# Gagabiro_main.net
KiCad netlist of a schematic drawn in Altium Designer
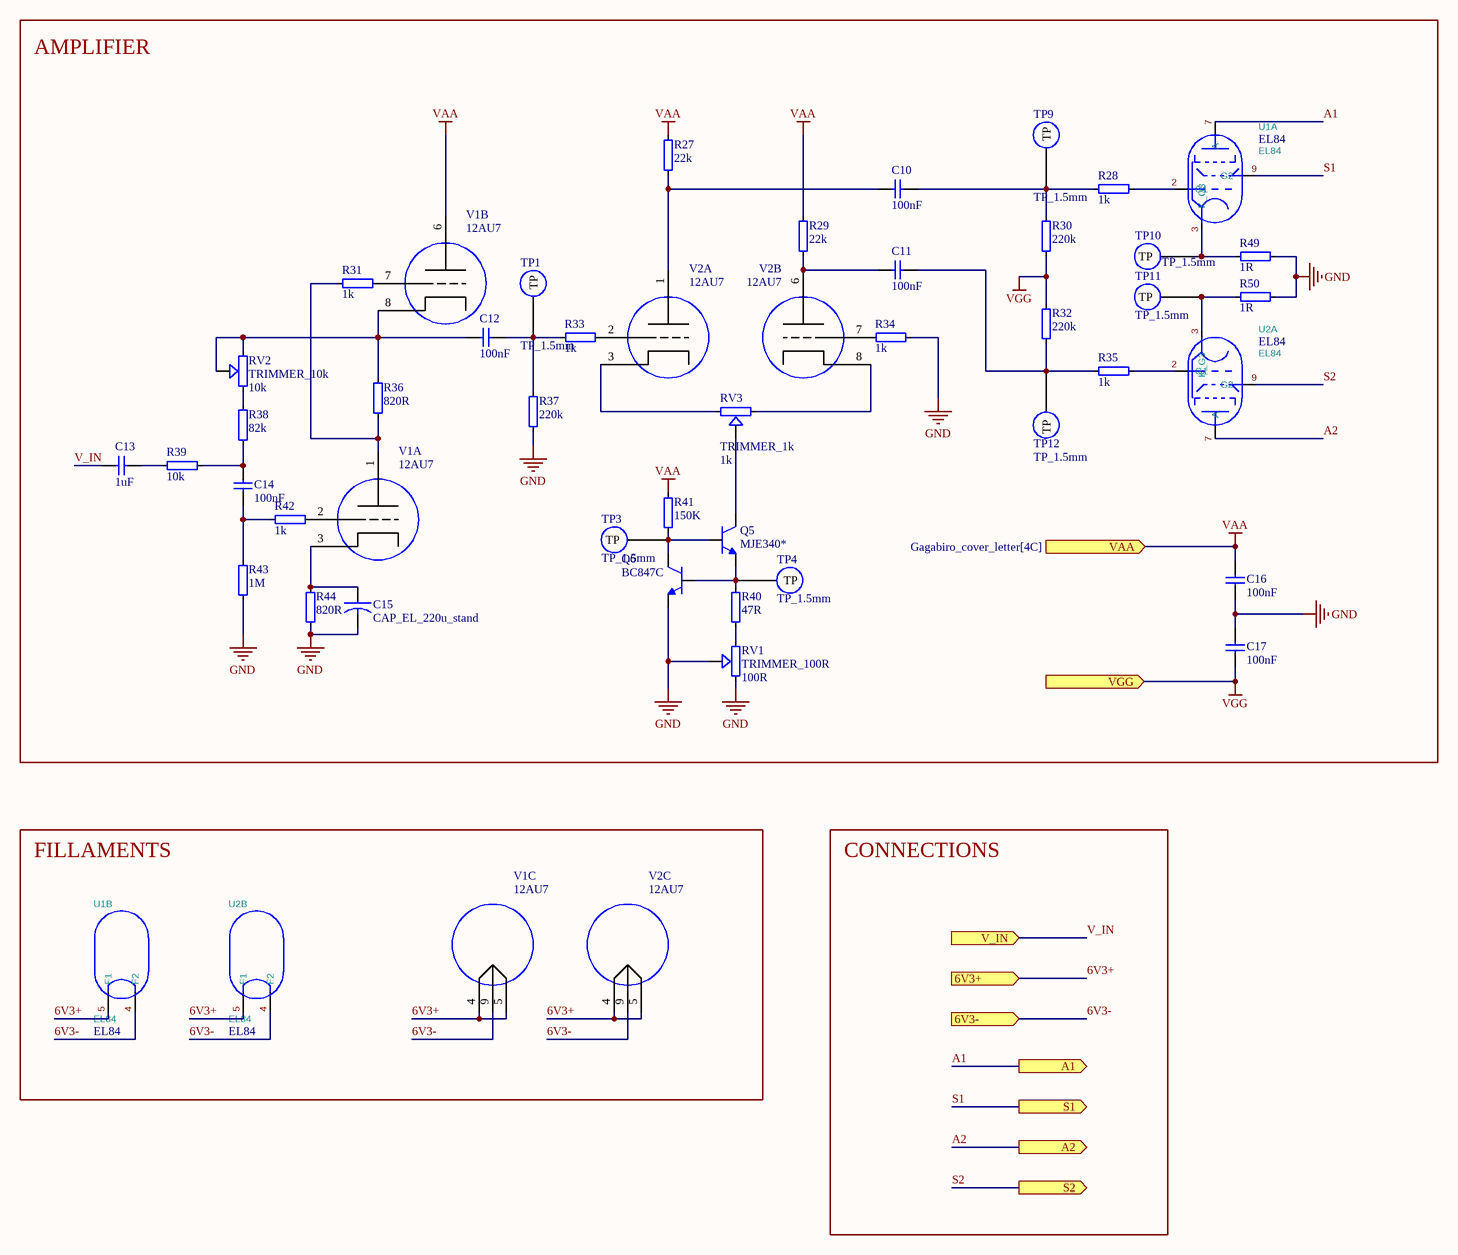
[diagram p0: Gagabiro_main.SchDoc]

(export (version "E")
  (design (tool "Eeschema 10.0.6"))
  (components
    (comp (ref "C10")
      (value "100nF")
      (footprint "CAP_panassonic_100n_450V")
      (description "Capacitor, Silver Mica")
      (fields (field (name "PART NUMBER") "CMICA_47PF"))
      (libsource (lib "Persephone_Integrated_Library") (part "CAP_POLY_100n"))
    )
    (comp (ref "C11")
      (value "100nF")
      (footprint "CAP_panassonic_100n_450V")
      (description "Capacitor, Silver Mica")
      (fields (field (name "PART NUMBER") "CMICA_47PF"))
      (libsource (lib "Persephone_Integrated_Library") (part "CAP_POLY_100n"))
    )
    (comp (ref "C12")
      (value "100nF")
      (footprint "CAP_panassonic_100n_450V")
      (description "Capacitor, Silver Mica")
      (fields (field (name "PART NUMBER") "CMICA_47PF"))
      (libsource (lib "Persephone_Integrated_Library") (part "CAP_POLY_100n"))
    )
    (comp (ref "C13")
      (value "1uF")
      (footprint "CAP_panassonic_1u_450V")
      (description "Capacitor, Silver Mica")
      (fields (field (name "PART NUMBER") "CMICA_47PF"))
      (libsource (lib "Persephone_Integrated_Library") (part "CAP_POLY_1u"))
    )
    (comp (ref "C14")
      (value "100nF")
      (footprint "CAP_panassonic_100n_450V")
      (description "Capacitor, Silver Mica")
      (fields (field (name "PART NUMBER") "CMICA_47PF"))
      (libsource (lib "Persephone_Integrated_Library") (part "CAP_POLY_100n"))
    )
    (comp (ref "C15")
      (value "CAP_EL_220u_stand")
      (footprint "CAPPRD500W50D630H1120_stand")
      (description "220F 16V Aluminum Electrolytic Capacitors Radial, Can 1000 Hrs @ 105C")
      (fields (field (name "MP") "EEU-HD1C221B") (field (name "MF") "Panasonic"))
      (libsource (lib "Persephone_Integrated_Library") (part "CAP_EL_220u_stand"))
    )
    (comp (ref "C16")
      (value "100nF")
      (footprint "CAP_panassonic_100n_450V")
      (description "Capacitor, Silver Mica")
      (fields (field (name "PART NUMBER") "CMICA_47PF"))
      (libsource (lib "Persephone_Integrated_Library") (part "CAP_POLY_100n"))
    )
    (comp (ref "C17")
      (value "100nF")
      (footprint "CAP_panassonic_100n_450V")
      (description "Capacitor, Silver Mica")
      (fields (field (name "PART NUMBER") "CMICA_47PF"))
      (libsource (lib "Persephone_Integrated_Library") (part "CAP_POLY_100n"))
    )
    (comp (ref "Q5")
      (value "MJE340*")
      (footprint "TO126")
      (description "Bipolar (BJT) Transistor NPN 300 V 500 mA - 20.8 W Through Hole SOT-32-3")
      (fields (field (name "MF") "STMicroelectronics") (field (name "MP") "MJE340"))
      (libsource (lib "Persephone_Integrated_Library") (part "MJE340*"))
    )
    (comp (ref "Q6")
      (value "BC847C")
      (footprint "TRANS_BC847C")
      (description "Bipolar (BJT) Transistor NPN 45 V 100 mA 300MHz 250 mW Surface Mount SOT-23-3 (TO-236)")
      (fields (field (name "MF") "Diotec Semiconductor"))
      (libsource (lib "Persephone") (part "BC847C"))
    )
    (comp (ref "R27")
      (value "22k")
      (footprint "RES_2W_vertical")
      (description "Resistor, 2W")
      (fields (field (name "PART NUMBER") "R2W") (field (name "AUTHOR") "colombari"))
      (libsource (lib "Gagabiro_Integrated_Library") (part "R_2W_vertical_22k"))
    )
    (comp (ref "R28")
      (value "1k")
      (footprint "RES_2W_vertical")
      (description "Resistor, 2W")
      (fields (field (name "PART NUMBER") "R2W") (field (name "AUTHOR") "colombari"))
      (libsource (lib "Gagabiro_Integrated_Library") (part "R_2W_vertical_1k"))
    )
    (comp (ref "R29")
      (value "22k")
      (footprint "RES_2W_vertical")
      (description "Resistor, 2W")
      (fields (field (name "PART NUMBER") "R2W") (field (name "AUTHOR") "colombari"))
      (libsource (lib "Gagabiro_Integrated_Library") (part "R_2W_vertical_22k"))
    )
    (comp (ref "R30")
      (value "220k")
      (footprint "RES_2W_vertical")
      (description "Resistor, 2W")
      (fields (field (name "PART NUMBER") "R2W") (field (name "AUTHOR") "colombari"))
      (libsource (lib "Gagabiro_Integrated_Library") (part "R_2W_vertical_220k"))
    )
    (comp (ref "R31")
      (value "1k")
      (footprint "RES_2W_vertical")
      (description "Resistor, 2W")
      (fields (field (name "PART NUMBER") "R2W") (field (name "AUTHOR") "colombari"))
      (libsource (lib "Gagabiro_Integrated_Library") (part "R_2W_vertical_1k"))
    )
    (comp (ref "R32")
      (value "220k")
      (footprint "RES_2W_vertical")
      (description "Resistor, 2W")
      (fields (field (name "PART NUMBER") "R2W") (field (name "AUTHOR") "colombari"))
      (libsource (lib "Gagabiro_Integrated_Library") (part "R_2W_vertical_220k"))
    )
    (comp (ref "R33")
      (value "1k")
      (footprint "RES_2W_vertical")
      (description "Resistor, 2W")
      (fields (field (name "PART NUMBER") "R2W") (field (name "AUTHOR") "colombari"))
      (libsource (lib "Gagabiro_Integrated_Library") (part "R_2W_vertical_1k"))
    )
    (comp (ref "R34")
      (value "1k")
      (footprint "RES_2W_vertical")
      (description "Resistor, 2W")
      (fields (field (name "PART NUMBER") "R2W") (field (name "AUTHOR") "colombari"))
      (libsource (lib "Gagabiro_Integrated_Library") (part "R_2W_vertical_1k"))
    )
    (comp (ref "R35")
      (value "1k")
      (footprint "RES_2W_vertical")
      (description "Resistor, 2W")
      (fields (field (name "PART NUMBER") "R2W") (field (name "AUTHOR") "colombari"))
      (libsource (lib "Gagabiro_Integrated_Library") (part "R_2W_vertical_1k"))
    )
    (comp (ref "R36")
      (value "820R")
      (footprint "RES_2W_vertical")
      (description "Resistor, 2W")
      (fields (field (name "PART NUMBER") "R2W") (field (name "AUTHOR") "colombari"))
      (libsource (lib "Gagabiro_Integrated_Library") (part "R_2W_vertical_820R"))
    )
    (comp (ref "R37")
      (value "220k")
      (footprint "RES_2W_vertical")
      (description "Resistor, 2W")
      (fields (field (name "PART NUMBER") "R2W") (field (name "AUTHOR") "colombari"))
      (libsource (lib "Gagabiro_Integrated_Library") (part "R_2W_vertical_220k"))
    )
    (comp (ref "R38")
      (value "82k")
      (footprint "RES_2W_vertical")
      (description "Resistor, 2W")
      (fields (field (name "PART NUMBER") "R2W") (field (name "AUTHOR") "colombari"))
      (libsource (lib "Gagabiro_Integrated_Library") (part "R_2W_vertical_82k"))
    )
    (comp (ref "R39")
      (value "10k")
      (footprint "RES_2W_vertical")
      (description "Resistor, 2W")
      (fields (field (name "PART NUMBER") "R2W") (field (name "AUTHOR") "colombari"))
      (libsource (lib "Gagabiro_Integrated_Library") (part "R_2W_vertical_10k"))
    )
    (comp (ref "R40")
      (value "47R")
      (footprint "RES_2W_vertical")
      (description "Resistor, 2W")
      (fields (field (name "PART NUMBER") "R2W") (field (name "AUTHOR") "colombari"))
      (libsource (lib "Gagabiro_Integrated_Library") (part "R_2W_vertical_47R"))
    )
    (comp (ref "R41")
      (value "150K")
      (footprint "RES_2W_vertical")
      (description "Resistor, 2W")
      (fields (field (name "PART NUMBER") "R2W") (field (name "AUTHOR") "colombari"))
      (libsource (lib "Gagabiro_Integrated_Library") (part "R_2W_vertical_150K"))
    )
    (comp (ref "R42")
      (value "1k")
      (footprint "RES_2W_vertical")
      (description "Resistor, 2W")
      (fields (field (name "PART NUMBER") "R2W") (field (name "AUTHOR") "colombari"))
      (libsource (lib "Gagabiro_Integrated_Library") (part "R_2W_vertical_1k"))
    )
    (comp (ref "R43")
      (value "1M")
      (footprint "RES_2W_vertical")
      (description "Resistor, 2W")
      (fields (field (name "PART NUMBER") "R2W") (field (name "AUTHOR") "colombari"))
      (libsource (lib "Gagabiro_Integrated_Library") (part "R_2W_vertical_1M"))
    )
    (comp (ref "R44")
      (value "820R")
      (footprint "RES_2W_vertical")
      (description "Resistor, 2W")
      (fields (field (name "PART NUMBER") "R2W") (field (name "AUTHOR") "colombari"))
      (libsource (lib "Gagabiro_Integrated_Library") (part "R_2W_vertical_820R"))
    )
    (comp (ref "R49")
      (value "1R")
      (footprint "RES_2W_vertical")
      (description "Resistor, 2W")
      (fields (field (name "PART NUMBER") "R2W") (field (name "AUTHOR") "colombari"))
      (libsource (lib "Gagabiro_Integrated_Library") (part "R_2W_vertical_1R"))
    )
    (comp (ref "R50")
      (value "1R")
      (footprint "RES_2W_vertical")
      (description "Resistor, 2W")
      (fields (field (name "PART NUMBER") "R2W") (field (name "AUTHOR") "colombari"))
      (libsource (lib "Gagabiro_Integrated_Library") (part "R_2W_vertical_1R"))
    )
    (comp (ref "RV1")
      (value "TRIMMER_100R")
      (footprint "TRIM_PV36W204C01B00 - duplicate")
      (description "TRIMMER")
      (fields
        (field (name "MF") "Bourns Electronics")
        (field (name "MP") "PV36W204C01B00.")
        (field (name "ALTIUM_VALUE") "100R")
      )
      (libsource (lib "Persephone") (part "TRIMMER_100R"))
    )
    (comp (ref "RV2")
      (value "TRIMMER_10k")
      (footprint "TRIM_PV36W204C01B00 - duplicate")
      (description "TRIMMER")
      (fields
        (field (name "MF") "Bourns Electronics")
        (field (name "MP") "PV36W204C01B00.")
        (field (name "ALTIUM_VALUE") "10k")
      )
      (libsource (lib "Persephone_Integrated_Library") (part "TRIMMER_10k"))
    )
    (comp (ref "RV3")
      (value "TRIMMER_1k")
      (footprint "TRIM_PV36W204C01B00 - duplicate")
      (description "TRIMMER")
      (fields
        (field (name "MF") "Bourns Electronics")
        (field (name "MP") "PV36W204C01B00.")
        (field (name "ALTIUM_VALUE") "1k")
      )
      (libsource (lib "Persephone_Integrated_Library") (part "TRIMMER_1k"))
    )
    (comp (ref "TP1")
      (value "TP_1.5mm")
      (footprint "test_point_1.5mm")
      (libsource (lib "Gagabiro_Integrated_Library") (part "TP_1.5mm"))
    )
    (comp (ref "TP3")
      (value "TP_1.5mm")
      (footprint "test_point_1.5mm")
      (libsource (lib "Gagabiro_Integrated_Library") (part "TP_1.5mm"))
    )
    (comp (ref "TP4")
      (value "TP_1.5mm")
      (footprint "test_point_1.5mm")
      (libsource (lib "Gagabiro_Integrated_Library") (part "TP_1.5mm"))
    )
    (comp (ref "TP9")
      (value "TP_1.5mm")
      (footprint "test_point_1.5mm")
      (libsource (lib "Gagabiro_Integrated_Library") (part "TP_1.5mm"))
    )
    (comp (ref "TP10")
      (value "TP_1.5mm")
      (footprint "test_point_1.5mm")
      (libsource (lib "Gagabiro_Integrated_Library") (part "TP_1.5mm"))
    )
    (comp (ref "TP11")
      (value "TP_1.5mm")
      (footprint "test_point_1.5mm")
      (libsource (lib "Gagabiro_Integrated_Library") (part "TP_1.5mm"))
    )
    (comp (ref "TP12")
      (value "TP_1.5mm")
      (footprint "test_point_1.5mm")
      (libsource (lib "Gagabiro_Integrated_Library") (part "TP_1.5mm"))
    )
    (comp (ref "U1")
      (value "EL84")
      (footprint "EL84")
      (fields (field (name "ALTIUM_VALUE") "EL84"))
      (libsource (lib "") (part "EL84_1"))
    )
    (comp (ref "U2")
      (value "EL84")
      (footprint "EL84")
      (fields (field (name "ALTIUM_VALUE") "EL84"))
      (libsource (lib "Gagabiro_Integrated_Library") (part "EL84"))
    )
    (comp (ref "V1")
      (value "12AU7")
      (footprint "12A_7")
      (description "TUNGSOL 12AU7 NEW PRD PREAMP TB")
      (fields (field (name "MF") "RCA") (field (name "MP") "12AX7"))
      (libsource (lib "Gagabiro_Integrated_Library") (part "12AU7"))
    )
    (comp (ref "V2")
      (value "12AU7")
      (footprint "12A_7")
      (description "TUNGSOL 12AU7 NEW PRD PREAMP TB")
      (fields (field (name "MF") "RCA") (field (name "MP") "12AX7"))
      (libsource (lib "") (part "12AU7_1"))
    )
  )
  (nets
    (net (code "1") (name "/6V3+") (class "Default")
      (node (ref "U1") (pin "5") (pinfunction "F1_5") (pintype "passive"))
      (node (ref "U2") (pin "5") (pinfunction "F1_5") (pintype "passive"))
      (node (ref "V1") (pin "4") (pinfunction "4_4") (pintype "passive"))
      (node (ref "V1") (pin "5") (pinfunction "5_5") (pintype "passive"))
      (node (ref "V2") (pin "4") (pinfunction "4_4") (pintype "passive"))
      (node (ref "V2") (pin "5") (pinfunction "5_5") (pintype "passive"))
    )
    (net (code "2") (name "/6V3-") (class "Default")
      (node (ref "U1") (pin "4") (pinfunction "F2_4") (pintype "passive"))
      (node (ref "U2") (pin "4") (pinfunction "F2_4") (pintype "passive"))
      (node (ref "V1") (pin "9") (pinfunction "9_9") (pintype "passive"))
      (node (ref "V2") (pin "9") (pinfunction "9_9") (pintype "passive"))
    )
    (net (code "3") (name "/A1") (class "Default")
      (node (ref "U1") (pin "7") (pinfunction "A_7") (pintype "passive"))
    )
    (net (code "4") (name "/A2") (class "Default")
      (node (ref "U2") (pin "7") (pinfunction "A_7") (pintype "passive"))
    )
    (net (code "5") (name "/S1") (class "Default")
      (node (ref "U1") (pin "9") (pinfunction "G2_9") (pintype "passive"))
    )
    (net (code "6") (name "/S2") (class "Default")
      (node (ref "U2") (pin "9") (pinfunction "G2_9") (pintype "passive"))
    )
    (net (code "7") (name "/V_IN") (class "Default")
      (node (ref "C13") (pin "1") (pinfunction "1_1") (pintype "passive"))
    )
    (net (code "8") (name "GND") (class "Default")
      (node (ref "C15") (pin "N") (pinfunction "N_N") (pintype "passive"))
      (node (ref "C16") (pin "1") (pinfunction "1_1") (pintype "passive"))
      (node (ref "C17") (pin "1") (pinfunction "1_1") (pintype "passive"))
      (node (ref "Q6") (pin "2") (pinfunction "E_2") (pintype "passive"))
      (node (ref "R34") (pin "2") (pinfunction "2_2") (pintype "passive"))
      (node (ref "R37") (pin "1") (pinfunction "1_1") (pintype "passive"))
      (node (ref "R43") (pin "1") (pinfunction "1_1") (pintype "passive"))
      (node (ref "R44") (pin "1") (pinfunction "1_1") (pintype "passive"))
      (node (ref "R49") (pin "2") (pinfunction "2_2") (pintype "passive"))
      (node (ref "R50") (pin "2") (pinfunction "2_2") (pintype "passive"))
      (node (ref "RV1") (pin "1") (pinfunction "1_1") (pintype "passive"))
      (node (ref "RV1") (pin "2") (pinfunction "2_2") (pintype "passive"))
    )
    (net (code "9") (name "Net-(C10-Pad1)") (class "Default")
      (node (ref "C10") (pin "1") (pinfunction "1_1") (pintype "passive"))
      (node (ref "R27") (pin "1") (pinfunction "1_1") (pintype "passive"))
      (node (ref "V2") (pin "1") (pinfunction "1_1") (pintype "passive"))
    )
    (net (code "10") (name "Net-(C11-Pad1)") (class "Default")
      (node (ref "C11") (pin "1") (pinfunction "1_1") (pintype "passive"))
      (node (ref "R29") (pin "1") (pinfunction "1_1") (pintype "passive"))
      (node (ref "V2") (pin "6") (pinfunction "6_6") (pintype "passive"))
    )
    (net (code "11") (name "Net-(C12-Pad1)") (class "Default")
      (node (ref "C12") (pin "1") (pinfunction "1_1") (pintype "passive"))
      (node (ref "R36") (pin "2") (pinfunction "2_2") (pintype "passive"))
      (node (ref "RV2") (pin "2") (pinfunction "2_2") (pintype "passive"))
      (node (ref "RV2") (pin "3") (pinfunction "3_3") (pintype "passive"))
      (node (ref "V1") (pin "8") (pinfunction "8_8") (pintype "passive"))
    )
    (net (code "12") (name "Net-(C13-Pad2)") (class "Default")
      (node (ref "C13") (pin "2") (pinfunction "2_2") (pintype "passive"))
      (node (ref "R39") (pin "1") (pinfunction "1_1") (pintype "passive"))
    )
    (net (code "13") (name "Net-(C14-Pad1)") (class "Default")
      (node (ref "C14") (pin "1") (pinfunction "1_1") (pintype "passive"))
      (node (ref "R42") (pin "1") (pinfunction "1_1") (pintype "passive"))
      (node (ref "R43") (pin "2") (pinfunction "2_2") (pintype "passive"))
    )
    (net (code "14") (name "Net-(C14-Pad2)") (class "Default")
      (node (ref "C14") (pin "2") (pinfunction "2_2") (pintype "passive"))
      (node (ref "R38") (pin "1") (pinfunction "1_1") (pintype "passive"))
      (node (ref "R39") (pin "2") (pinfunction "2_2") (pintype "passive"))
    )
    (net (code "15") (name "Net-(C15-PadP)") (class "Default")
      (node (ref "C15") (pin "P") (pinfunction "P_P") (pintype "passive"))
      (node (ref "R44") (pin "2") (pinfunction "2_2") (pintype "passive"))
      (node (ref "V1") (pin "3") (pinfunction "3_3") (pintype "passive"))
    )
    (net (code "16") (name "Net-(Q5-B)") (class "Default")
      (node (ref "Q5") (pin "3") (pinfunction "B_3") (pintype "passive"))
      (node (ref "Q6") (pin "3") (pinfunction "C_3") (pintype "passive"))
      (node (ref "R41") (pin "1") (pinfunction "1_1") (pintype "passive"))
      (node (ref "TP3") (pin "1") (pinfunction "TP_1") (pintype "passive"))
    )
    (net (code "17") (name "Net-(Q5-C)") (class "Default")
      (node (ref "Q5") (pin "2") (pinfunction "C_2") (pintype "passive"))
      (node (ref "RV3") (pin "2") (pinfunction "2_2") (pintype "passive"))
    )
    (net (code "18") (name "Net-(Q5-E)") (class "Default")
      (node (ref "Q5") (pin "1") (pinfunction "E_1") (pintype "passive"))
      (node (ref "Q6") (pin "1") (pinfunction "B_1") (pintype "passive"))
      (node (ref "R40") (pin "2") (pinfunction "2_2") (pintype "passive"))
      (node (ref "TP4") (pin "1") (pinfunction "TP_1") (pintype "passive"))
    )
    (net (code "19") (name "Net-(R31-Pad1)") (class "Default")
      (node (ref "R31") (pin "1") (pinfunction "1_1") (pintype "passive"))
      (node (ref "R36") (pin "1") (pinfunction "1_1") (pintype "passive"))
      (node (ref "V1") (pin "1") (pinfunction "1_1") (pintype "passive"))
    )
    (net (code "20") (name "Net-(R31-Pad2)") (class "Default")
      (node (ref "R31") (pin "2") (pinfunction "2_2") (pintype "passive"))
      (node (ref "V1") (pin "7") (pinfunction "7_7") (pintype "passive"))
    )
    (net (code "21") (name "Net-(R33-Pad2)") (class "Default")
      (node (ref "R33") (pin "2") (pinfunction "2_2") (pintype "passive"))
      (node (ref "V2") (pin "2") (pinfunction "2_2") (pintype "passive"))
    )
    (net (code "22") (name "Net-(R34-Pad1)") (class "Default")
      (node (ref "R34") (pin "1") (pinfunction "1_1") (pintype "passive"))
      (node (ref "V2") (pin "7") (pinfunction "7_7") (pintype "passive"))
    )
    (net (code "23") (name "Net-(R38-Pad2)") (class "Default")
      (node (ref "R38") (pin "2") (pinfunction "2_2") (pintype "passive"))
      (node (ref "RV2") (pin "1") (pinfunction "1_1") (pintype "passive"))
    )
    (net (code "24") (name "Net-(R40-Pad1)") (class "Default")
      (node (ref "R40") (pin "1") (pinfunction "1_1") (pintype "passive"))
      (node (ref "RV1") (pin "3") (pinfunction "3_3") (pintype "passive"))
    )
    (net (code "25") (name "Net-(R42-Pad2)") (class "Default")
      (node (ref "R42") (pin "2") (pinfunction "2_2") (pintype "passive"))
      (node (ref "V1") (pin "2") (pinfunction "2_2") (pintype "passive"))
    )
    (net (code "26") (name "Net-(RV3-Pad1)") (class "Default")
      (node (ref "RV3") (pin "1") (pinfunction "1_1") (pintype "passive"))
      (node (ref "V2") (pin "8") (pinfunction "8_8") (pintype "passive"))
    )
    (net (code "27") (name "Net-(RV3-Pad3)") (class "Default")
      (node (ref "RV3") (pin "3") (pinfunction "3_3") (pintype "passive"))
      (node (ref "V2") (pin "3") (pinfunction "3_3") (pintype "passive"))
    )
    (net (code "28") (name "Net-(TP1-TP)") (class "Default")
      (node (ref "C12") (pin "2") (pinfunction "2_2") (pintype "passive"))
      (node (ref "R33") (pin "1") (pinfunction "1_1") (pintype "passive"))
      (node (ref "R37") (pin "2") (pinfunction "2_2") (pintype "passive"))
      (node (ref "TP1") (pin "1") (pinfunction "TP_1") (pintype "passive"))
    )
    (net (code "29") (name "Net-(TP9-TP)") (class "Default")
      (node (ref "C10") (pin "2") (pinfunction "2_2") (pintype "passive"))
      (node (ref "R28") (pin "1") (pinfunction "1_1") (pintype "passive"))
      (node (ref "R30") (pin "2") (pinfunction "2_2") (pintype "passive"))
      (node (ref "TP9") (pin "1") (pinfunction "TP_1") (pintype "passive"))
    )
    (net (code "30") (name "Net-(TP10-TP)") (class "Default")
      (node (ref "R49") (pin "1") (pinfunction "1_1") (pintype "passive"))
      (node (ref "TP10") (pin "1") (pinfunction "TP_1") (pintype "passive"))
      (node (ref "U1") (pin "3") (pinfunction "K_G3_3") (pintype "passive"))
    )
    (net (code "31") (name "Net-(TP11-TP)") (class "Default")
      (node (ref "R50") (pin "1") (pinfunction "1_1") (pintype "passive"))
      (node (ref "TP11") (pin "1") (pinfunction "TP_1") (pintype "passive"))
      (node (ref "U2") (pin "3") (pinfunction "K_G3_3") (pintype "passive"))
    )
    (net (code "32") (name "Net-(TP12-TP)") (class "Default")
      (node (ref "C11") (pin "2") (pinfunction "2_2") (pintype "passive"))
      (node (ref "R32") (pin "2") (pinfunction "2_2") (pintype "passive"))
      (node (ref "R35") (pin "1") (pinfunction "1_1") (pintype "passive"))
      (node (ref "TP12") (pin "1") (pinfunction "TP_1") (pintype "passive"))
    )
    (net (code "33") (name "Net-(U1A-G1)") (class "Default")
      (node (ref "R28") (pin "2") (pinfunction "2_2") (pintype "passive"))
      (node (ref "U1") (pin "2") (pinfunction "G1_2") (pintype "passive"))
    )
    (net (code "34") (name "Net-(U2A-G1)") (class "Default")
      (node (ref "R35") (pin "2") (pinfunction "2_2") (pintype "passive"))
      (node (ref "U2") (pin "2") (pinfunction "G1_2") (pintype "passive"))
    )
    (net (code "35") (name "VAA") (class "Default")
      (node (ref "C16") (pin "2") (pinfunction "2_2") (pintype "passive"))
      (node (ref "R27") (pin "2") (pinfunction "2_2") (pintype "passive"))
      (node (ref "R29") (pin "2") (pinfunction "2_2") (pintype "passive"))
      (node (ref "R41") (pin "2") (pinfunction "2_2") (pintype "passive"))
      (node (ref "V1") (pin "6") (pinfunction "6_6") (pintype "passive"))
    )
    (net (code "36") (name "VGG") (class "Default")
      (node (ref "C17") (pin "2") (pinfunction "2_2") (pintype "passive"))
      (node (ref "R30") (pin "1") (pinfunction "1_1") (pintype "passive"))
      (node (ref "R32") (pin "1") (pinfunction "1_1") (pintype "passive"))
    )
  )
)
